# VT_WRP.net
KiCad netlist of a schematic drawn in Altium Designer
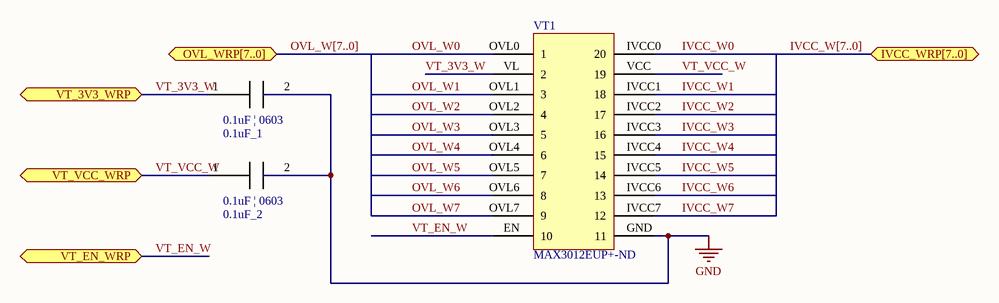
[diagram p0: VT_WRP.SchDoc]

(export (version "E")
  (design (tool "Eeschema 10.0.6"))
  (components
    (comp (ref "0.1uF_1")
      (value "0.1uF_0603")
      (footprint "0.1uF_0603")
      (libsource (lib "DUTBoard") (part "0.1uF_0603"))
    )
    (comp (ref "0.1uF_2")
      (value "0.1uF_0603")
      (footprint "0.1uF_0603")
      (libsource (lib "DUTBoard") (part "0.1uF_0603"))
    )
    (comp (ref "VT1")
      (value "MAX3012EUP+")
      (footprint "VT_TSSOP20")
      (description "IC TRANSLATOR LEVEL 8CH 20-TSSOP")
      (fields
        (field (name "MANUFACTURER") "Maxim Integrated")
        (field (name "SUPPLIER PART NUMBER 1") "MAX3012EUP+-ND")
      )
      (libsource (lib "DUTBoard") (part "MAX3012EUP+"))
    )
  )
  (nets
    (net (code "1") (name "/IVCC_W0") (class "Default")
      (node (ref "VT1") (pin "IVCC0") (pinfunction "20_IVCC0") (pintype "passive"))
    )
    (net (code "2") (name "/IVCC_W1") (class "Default")
      (node (ref "VT1") (pin "IVCC1") (pinfunction "18_IVCC1") (pintype "passive"))
    )
    (net (code "3") (name "/IVCC_W2") (class "Default")
      (node (ref "VT1") (pin "IVCC2") (pinfunction "17_IVCC2") (pintype "passive"))
    )
    (net (code "4") (name "/IVCC_W3") (class "Default")
      (node (ref "VT1") (pin "IVCC3") (pinfunction "16_IVCC3") (pintype "passive"))
    )
    (net (code "5") (name "/IVCC_W4") (class "Default")
      (node (ref "VT1") (pin "IVCC4") (pinfunction "15_IVCC4") (pintype "passive"))
    )
    (net (code "6") (name "/IVCC_W5") (class "Default")
      (node (ref "VT1") (pin "IVCC5") (pinfunction "14_IVCC5") (pintype "passive"))
    )
    (net (code "7") (name "/IVCC_W6") (class "Default")
      (node (ref "VT1") (pin "IVCC6") (pinfunction "13_IVCC6") (pintype "passive"))
    )
    (net (code "8") (name "/IVCC_W7") (class "Default")
      (node (ref "VT1") (pin "IVCC7") (pinfunction "12_IVCC7") (pintype "passive"))
    )
    (net (code "10") (name "/OVL_W0") (class "Default")
      (node (ref "VT1") (pin "OVL0") (pinfunction "1_OVL0") (pintype "passive"))
    )
    (net (code "11") (name "/OVL_W1") (class "Default")
      (node (ref "VT1") (pin "OVL1") (pinfunction "3_OVL1") (pintype "passive"))
    )
    (net (code "12") (name "/OVL_W2") (class "Default")
      (node (ref "VT1") (pin "OVL2") (pinfunction "4_OVL2") (pintype "passive"))
    )
    (net (code "13") (name "/OVL_W3") (class "Default")
      (node (ref "VT1") (pin "OVL3") (pinfunction "5_OVL3") (pintype "passive"))
    )
    (net (code "14") (name "/OVL_W4") (class "Default")
      (node (ref "VT1") (pin "OVL4") (pinfunction "6_OVL4") (pintype "passive"))
    )
    (net (code "15") (name "/OVL_W5") (class "Default")
      (node (ref "VT1") (pin "OVL5") (pinfunction "7_OVL5") (pintype "passive"))
    )
    (net (code "16") (name "/OVL_W6") (class "Default")
      (node (ref "VT1") (pin "OVL6") (pinfunction "8_OVL6") (pintype "passive"))
    )
    (net (code "17") (name "/OVL_W7") (class "Default")
      (node (ref "VT1") (pin "OVL7") (pinfunction "9_OVL7") (pintype "passive"))
    )
    (net (code "19") (name "/VT_3V3_W") (class "Default")
      (node (ref "0.1uF_1") (pin "1") (pinfunction "1_1") (pintype "passive"))
      (node (ref "VT1") (pin "VL") (pinfunction "2_VL") (pintype "passive"))
    )
    (net (code "20") (name "/VT_EN_W") (class "Default")
      (node (ref "VT1") (pin "EN") (pinfunction "10_EN") (pintype "passive"))
    )
    (net (code "21") (name "/VT_VCC_W") (class "Default")
      (node (ref "0.1uF_2") (pin "1") (pinfunction "1_1") (pintype "passive"))
      (node (ref "VT1") (pin "VCC") (pinfunction "19_VCC") (pintype "passive"))
    )
    (net (code "22") (name "GND") (class "Default")
      (node (ref "0.1uF_1") (pin "2") (pinfunction "2_2") (pintype "passive"))
      (node (ref "0.1uF_2") (pin "2") (pinfunction "2_2") (pintype "passive"))
      (node (ref "VT1") (pin "GND") (pinfunction "11_GND") (pintype "passive"))
    )
  )
)
